# LMD18200.net
KiCad netlist of a schematic drawn in EAGLE
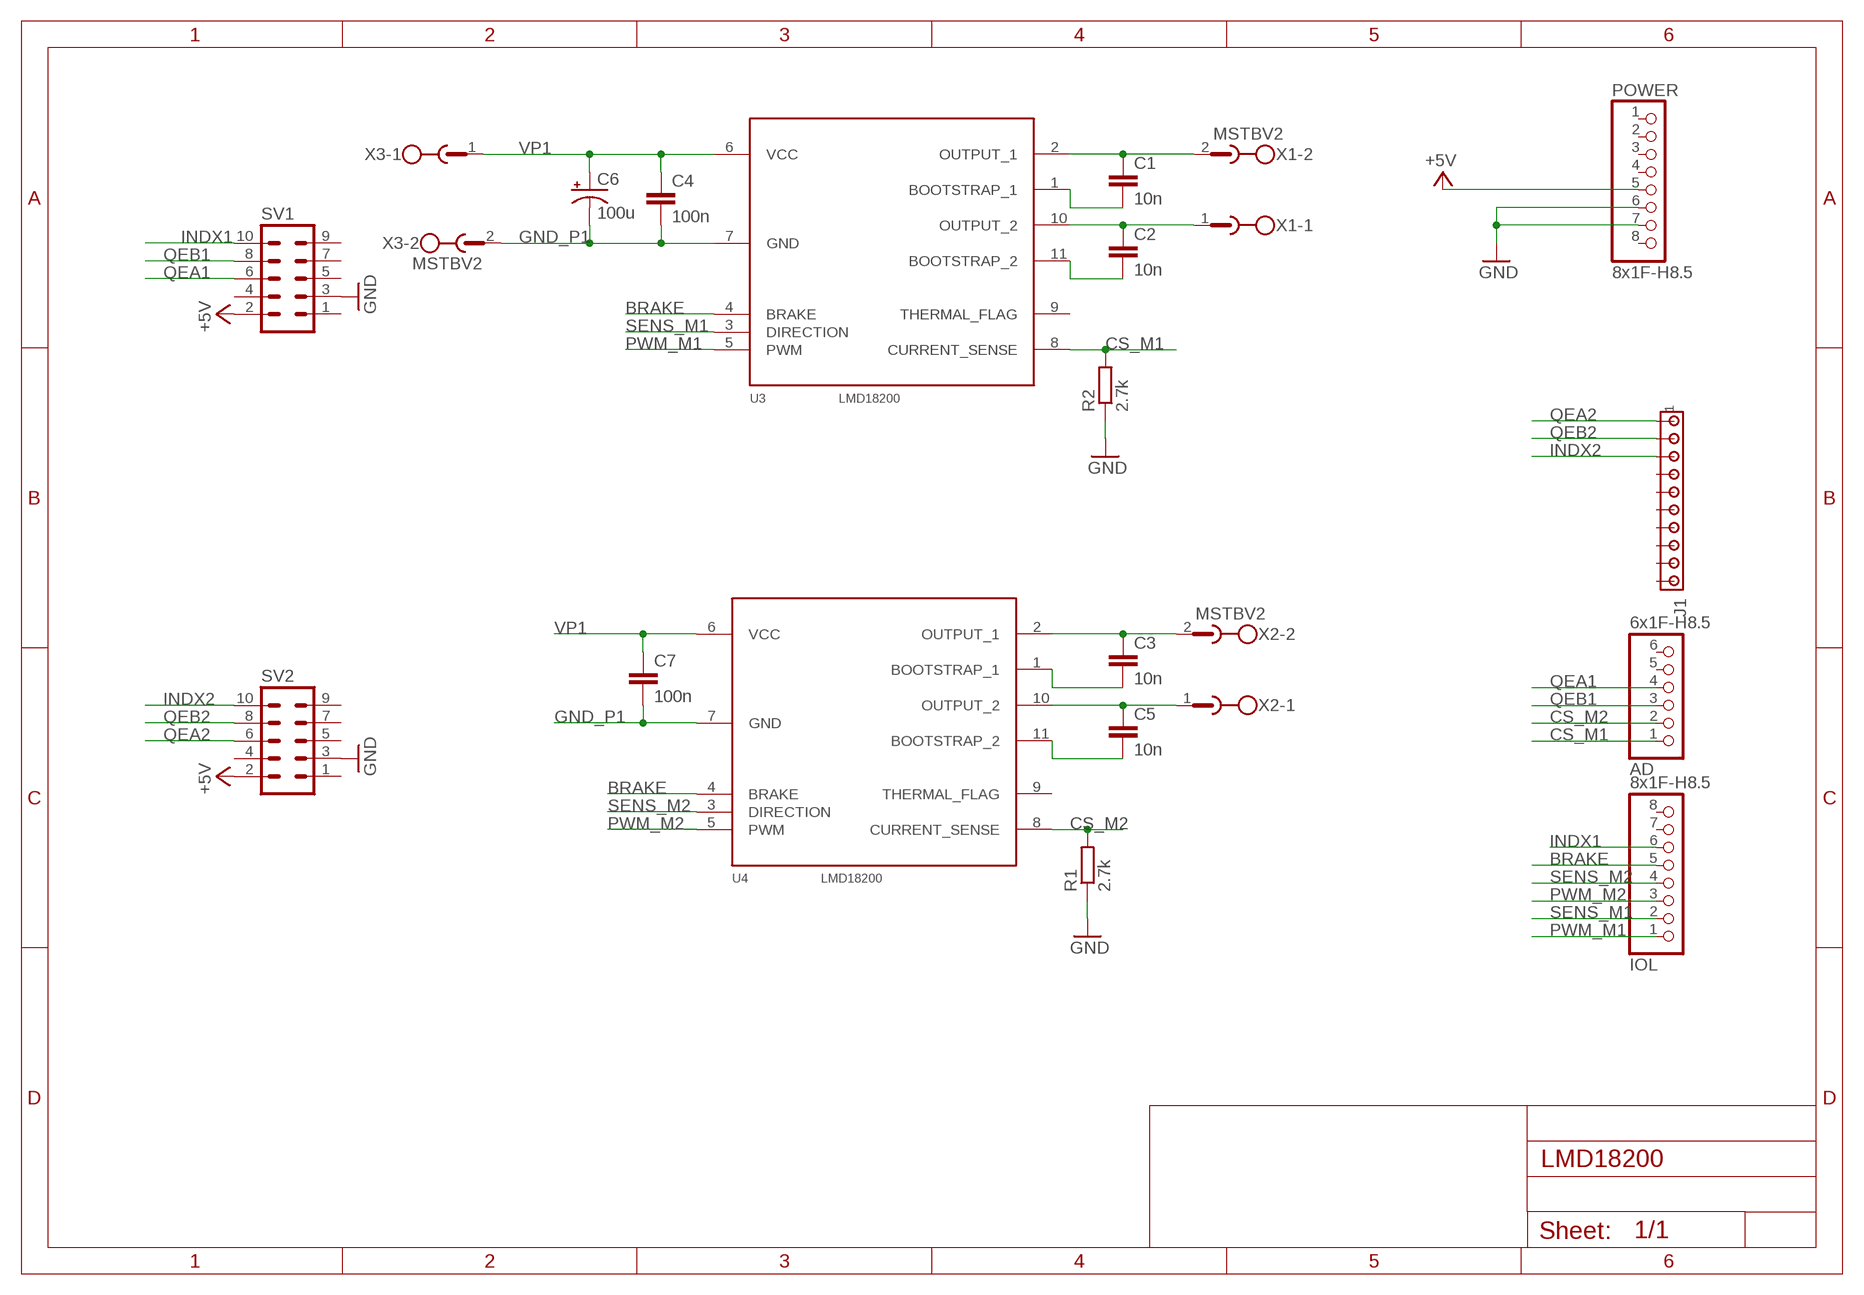
[diagram p0: schematic, sheet 1]

(export (version "E")
  (design (tool "Eeschema 10.0.6"))
  (components
    (comp (ref "AD")
      (value "6x1F-H8.5")
      (footprint "eagle-import:1X06")
      (libsource (lib "eagle-import") (part "PINHD-1X6"))
    )
    (comp (ref "C1")
      (value "10n")
      (footprint "eagle-import:C0603")
      (libsource (lib "eagle-import") (part "C-EUC0603"))
    )
    (comp (ref "C2")
      (value "10n")
      (footprint "eagle-import:C0603")
      (libsource (lib "eagle-import") (part "C-EUC0603"))
    )
    (comp (ref "C3")
      (value "10n")
      (footprint "eagle-import:C0603")
      (libsource (lib "eagle-import") (part "C-EUC0603"))
    )
    (comp (ref "C4")
      (value "100n")
      (footprint "eagle-import:C0603")
      (libsource (lib "eagle-import") (part "C-EUC0603"))
    )
    (comp (ref "C5")
      (value "10n")
      (footprint "eagle-import:C0603")
      (libsource (lib "eagle-import") (part "C-EUC0603"))
    )
    (comp (ref "C6")
      (value "100u")
      (footprint "eagle-import:E5-13")
      (libsource (lib "eagle-import") (part "CPOL-USE5-13"))
    )
    (comp (ref "C7")
      (value "100n")
      (footprint "eagle-import:C0603")
      (libsource (lib "eagle-import") (part "C-EUC0603"))
    )
    (comp (ref "IOL")
      (value "8x1F-H8.5")
      (footprint "eagle-import:1X08")
      (libsource (lib "eagle-import") (part "PINHD-1X8"))
    )
    (comp (ref "J1")
      (value "MTA10-100")
      (footprint "eagle-import:10X10MTA")
      (libsource (lib "eagle-import") (part "MTA10-100"))
    )
    (comp (ref "POWER")
      (value "8x1F-H8.5")
      (footprint "eagle-import:1X08")
      (libsource (lib "eagle-import") (part "PINHD-1X8"))
    )
    (comp (ref "R1")
      (value "2.7k")
      (footprint "eagle-import:R0805")
      (libsource (lib "eagle-import") (part "R-EU_R0805"))
    )
    (comp (ref "R2")
      (value "2.7k")
      (footprint "eagle-import:R0805")
      (libsource (lib "eagle-import") (part "R-EU_R0805"))
    )
    (comp (ref "SV1")
      (value "ML10L")
      (footprint "eagle-import:ML10L")
      (libsource (lib "eagle-import") (part "ML10L"))
    )
    (comp (ref "SV2")
      (value "ML10L")
      (footprint "eagle-import:ML10L")
      (libsource (lib "eagle-import") (part "ML10L"))
    )
    (comp (ref "U3")
      (value "LMD18200")
      (footprint "eagle-import:TO-220-11_C")
      (libsource (lib "eagle-import") (part "LMD18200"))
    )
    (comp (ref "U4")
      (value "LMD18200")
      (footprint "eagle-import:TO-220-11_C")
      (libsource (lib "eagle-import") (part "LMD18200"))
    )
    (comp (ref "X1")
      (value "MSTBV2")
      (footprint "eagle-import:MSTBV2")
      (fields (field (name "MPN") "MSTBV 2,5/2-GF-5.08"))
      (libsource (lib "eagle-import") (part "MSTBV2"))
    )
    (comp (ref "X2")
      (value "MSTBV2")
      (footprint "eagle-import:MSTBV2")
      (fields (field (name "MPN") "MSTBV 2,5/2-GF-5.08"))
      (libsource (lib "eagle-import") (part "MSTBV2"))
    )
    (comp (ref "X3")
      (value "MSTBV2")
      (footprint "eagle-import:MSTBV2")
      (fields (field (name "MPN") "MSTBV 2,5/2-GF-5.08"))
      (libsource (lib "eagle-import") (part "MSTBV2"))
    )
  )
  (nets
    (net (code "1") (name "+5V") (class "Default")
      (node (ref "POWER") (pin "5") (pinfunction "5_5") (pintype "passive"))
      (node (ref "SV1") (pin "2") (pinfunction "2_2") (pintype "passive"))
      (node (ref "SV2") (pin "2") (pinfunction "2_2") (pintype "passive"))
    )
    (net (code "2") (name "/BRAKE") (class "Default")
      (node (ref "IOL") (pin "5") (pinfunction "5_5") (pintype "passive"))
      (node (ref "U3") (pin "4") (pinfunction "BRAKE_4") (pintype "input"))
      (node (ref "U4") (pin "4") (pinfunction "BRAKE_4") (pintype "input"))
    )
    (net (code "3") (name "/CS_M1") (class "Default")
      (node (ref "AD") (pin "1") (pinfunction "1_1") (pintype "passive"))
      (node (ref "R2") (pin "2") (pinfunction "2_2") (pintype "passive"))
      (node (ref "U3") (pin "8") (pinfunction "CURRENT_SENSE_8") (pintype "output"))
    )
    (net (code "4") (name "/CS_M2") (class "Default")
      (node (ref "AD") (pin "2") (pinfunction "2_2") (pintype "passive"))
      (node (ref "R1") (pin "2") (pinfunction "2_2") (pintype "passive"))
      (node (ref "U4") (pin "8") (pinfunction "CURRENT_SENSE_8") (pintype "output"))
    )
    (net (code "5") (name "/GND_P1") (class "Default")
      (node (ref "C4") (pin "2") (pinfunction "2_2") (pintype "passive"))
      (node (ref "C6") (pin "-") (pinfunction "-_-") (pintype "passive"))
      (node (ref "C7") (pin "2") (pinfunction "2_2") (pintype "passive"))
      (node (ref "U3") (pin "7") (pinfunction "GND_7") (pintype "power_in"))
      (node (ref "U4") (pin "7") (pinfunction "GND_7") (pintype "power_in"))
      (node (ref "X3") (pin "2") (pinfunction "1_2") (pintype "passive"))
    )
    (net (code "6") (name "/INDX1") (class "Default")
      (node (ref "IOL") (pin "6") (pinfunction "6_6") (pintype "passive"))
      (node (ref "SV1") (pin "10") (pinfunction "10_10") (pintype "passive"))
    )
    (net (code "7") (name "/INDX2") (class "Default")
      (node (ref "J1") (pin "3") (pinfunction "3_3") (pintype "passive"))
      (node (ref "SV2") (pin "10") (pinfunction "10_10") (pintype "passive"))
    )
    (net (code "8") (name "/PWM_M1") (class "Default")
      (node (ref "IOL") (pin "1") (pinfunction "1_1") (pintype "passive"))
      (node (ref "U3") (pin "5") (pinfunction "PWM_5") (pintype "input"))
    )
    (net (code "9") (name "/PWM_M2") (class "Default")
      (node (ref "IOL") (pin "3") (pinfunction "3_3") (pintype "passive"))
      (node (ref "U4") (pin "5") (pinfunction "PWM_5") (pintype "input"))
    )
    (net (code "10") (name "/QEA1") (class "Default")
      (node (ref "AD") (pin "4") (pinfunction "4_4") (pintype "passive"))
      (node (ref "SV1") (pin "6") (pinfunction "6_6") (pintype "passive"))
    )
    (net (code "11") (name "/QEA2") (class "Default")
      (node (ref "J1") (pin "1") (pinfunction "1_1") (pintype "passive"))
      (node (ref "SV2") (pin "6") (pinfunction "6_6") (pintype "passive"))
    )
    (net (code "12") (name "/QEB1") (class "Default")
      (node (ref "AD") (pin "3") (pinfunction "3_3") (pintype "passive"))
      (node (ref "SV1") (pin "8") (pinfunction "8_8") (pintype "passive"))
    )
    (net (code "13") (name "/QEB2") (class "Default")
      (node (ref "J1") (pin "2") (pinfunction "2_2") (pintype "passive"))
      (node (ref "SV2") (pin "8") (pinfunction "8_8") (pintype "passive"))
    )
    (net (code "14") (name "/SENS_M1") (class "Default")
      (node (ref "IOL") (pin "2") (pinfunction "2_2") (pintype "passive"))
      (node (ref "U3") (pin "3") (pinfunction "DIRECTION_3") (pintype "input"))
    )
    (net (code "15") (name "/SENS_M2") (class "Default")
      (node (ref "IOL") (pin "4") (pinfunction "4_4") (pintype "passive"))
      (node (ref "U4") (pin "3") (pinfunction "DIRECTION_3") (pintype "input"))
    )
    (net (code "16") (name "/VP1") (class "Default")
      (node (ref "C4") (pin "1") (pinfunction "1_1") (pintype "passive"))
      (node (ref "C6") (pin "+") (pinfunction "+_+") (pintype "passive"))
      (node (ref "C7") (pin "1") (pinfunction "1_1") (pintype "passive"))
      (node (ref "U3") (pin "6") (pinfunction "VCC_6") (pintype "power_in"))
      (node (ref "U4") (pin "6") (pinfunction "VCC_6") (pintype "power_in"))
      (node (ref "X3") (pin "1") (pinfunction "1_1") (pintype "passive"))
    )
    (net (code "17") (name "GND") (class "Default")
      (node (ref "POWER") (pin "6") (pinfunction "6_6") (pintype "passive"))
      (node (ref "POWER") (pin "7") (pinfunction "7_7") (pintype "passive"))
      (node (ref "R1") (pin "1") (pinfunction "1_1") (pintype "passive"))
      (node (ref "R2") (pin "1") (pinfunction "1_1") (pintype "passive"))
      (node (ref "SV1") (pin "3") (pinfunction "3_3") (pintype "passive"))
      (node (ref "SV2") (pin "3") (pinfunction "3_3") (pintype "passive"))
    )
    (net (code "18") (name "Net-(U3-BOOTSTRAP_1)") (class "Default")
      (node (ref "C1") (pin "2") (pinfunction "2_2") (pintype "passive"))
      (node (ref "U3") (pin "1") (pinfunction "BOOTSTRAP_1_1") (pintype "output"))
    )
    (net (code "19") (name "Net-(U3-BOOTSTRAP_2)") (class "Default")
      (node (ref "C2") (pin "2") (pinfunction "2_2") (pintype "passive"))
      (node (ref "U3") (pin "11") (pinfunction "BOOTSTRAP_2_11") (pintype "output"))
    )
    (net (code "20") (name "Net-(U3-OUTPUT_1)") (class "Default")
      (node (ref "C1") (pin "1") (pinfunction "1_1") (pintype "passive"))
      (node (ref "U3") (pin "2") (pinfunction "OUTPUT_1_2") (pintype "output"))
      (node (ref "X1") (pin "2") (pinfunction "1_2") (pintype "passive"))
    )
    (net (code "21") (name "Net-(U3-OUTPUT_2)") (class "Default")
      (node (ref "C2") (pin "1") (pinfunction "1_1") (pintype "passive"))
      (node (ref "U3") (pin "10") (pinfunction "OUTPUT_2_10") (pintype "output"))
      (node (ref "X1") (pin "1") (pinfunction "1_1") (pintype "passive"))
    )
    (net (code "22") (name "Net-(U4-BOOTSTRAP_1)") (class "Default")
      (node (ref "C3") (pin "2") (pinfunction "2_2") (pintype "passive"))
      (node (ref "U4") (pin "1") (pinfunction "BOOTSTRAP_1_1") (pintype "output"))
    )
    (net (code "23") (name "Net-(U4-BOOTSTRAP_2)") (class "Default")
      (node (ref "C5") (pin "2") (pinfunction "2_2") (pintype "passive"))
      (node (ref "U4") (pin "11") (pinfunction "BOOTSTRAP_2_11") (pintype "output"))
    )
    (net (code "24") (name "Net-(U4-OUTPUT_1)") (class "Default")
      (node (ref "C3") (pin "1") (pinfunction "1_1") (pintype "passive"))
      (node (ref "U4") (pin "2") (pinfunction "OUTPUT_1_2") (pintype "output"))
      (node (ref "X2") (pin "2") (pinfunction "1_2") (pintype "passive"))
    )
    (net (code "25") (name "Net-(U4-OUTPUT_2)") (class "Default")
      (node (ref "C5") (pin "1") (pinfunction "1_1") (pintype "passive"))
      (node (ref "U4") (pin "10") (pinfunction "OUTPUT_2_10") (pintype "output"))
      (node (ref "X2") (pin "1") (pinfunction "1_1") (pintype "passive"))
    )
    (net (code "26") (name "unconnected-(AD-Pad5)") (class "Default")
      (node (ref "AD") (pin "5") (pinfunction "5_5") (pintype "passive"))
    )
    (net (code "27") (name "unconnected-(AD-Pad6)") (class "Default")
      (node (ref "AD") (pin "6") (pinfunction "6_6") (pintype "passive"))
    )
    (net (code "28") (name "unconnected-(IOL-Pad7)") (class "Default")
      (node (ref "IOL") (pin "7") (pinfunction "7_7") (pintype "passive"))
    )
    (net (code "29") (name "unconnected-(IOL-Pad8)") (class "Default")
      (node (ref "IOL") (pin "8") (pinfunction "8_8") (pintype "passive"))
    )
    (net (code "30") (name "unconnected-(J1-Pad4)") (class "Default")
      (node (ref "J1") (pin "4") (pinfunction "4_4") (pintype "passive"))
    )
    (net (code "31") (name "unconnected-(J1-Pad5)") (class "Default")
      (node (ref "J1") (pin "5") (pinfunction "5_5") (pintype "passive"))
    )
    (net (code "32") (name "unconnected-(J1-Pad6)") (class "Default")
      (node (ref "J1") (pin "6") (pinfunction "6_6") (pintype "passive"))
    )
    (net (code "33") (name "unconnected-(J1-Pad7)") (class "Default")
      (node (ref "J1") (pin "7") (pinfunction "7_7") (pintype "passive"))
    )
    (net (code "34") (name "unconnected-(J1-Pad8)") (class "Default")
      (node (ref "J1") (pin "8") (pinfunction "8_8") (pintype "passive"))
    )
    (net (code "35") (name "unconnected-(J1-Pad9)") (class "Default")
      (node (ref "J1") (pin "9") (pinfunction "9_9") (pintype "passive"))
    )
    (net (code "36") (name "unconnected-(J1-Pad10)") (class "Default")
      (node (ref "J1") (pin "10") (pinfunction "10_10") (pintype "passive"))
    )
    (net (code "37") (name "unconnected-(POWER-Pad1)") (class "Default")
      (node (ref "POWER") (pin "1") (pinfunction "1_1") (pintype "passive"))
    )
    (net (code "38") (name "unconnected-(POWER-Pad2)") (class "Default")
      (node (ref "POWER") (pin "2") (pinfunction "2_2") (pintype "passive"))
    )
    (net (code "39") (name "unconnected-(POWER-Pad3)") (class "Default")
      (node (ref "POWER") (pin "3") (pinfunction "3_3") (pintype "passive"))
    )
    (net (code "40") (name "unconnected-(POWER-Pad4)") (class "Default")
      (node (ref "POWER") (pin "4") (pinfunction "4_4") (pintype "passive"))
    )
    (net (code "41") (name "unconnected-(POWER-Pad8)") (class "Default")
      (node (ref "POWER") (pin "8") (pinfunction "8_8") (pintype "passive"))
    )
    (net (code "42") (name "unconnected-(SV1-Pad1)") (class "Default")
      (node (ref "SV1") (pin "1") (pinfunction "1_1") (pintype "passive"))
    )
    (net (code "43") (name "unconnected-(SV1-Pad4)") (class "Default")
      (node (ref "SV1") (pin "4") (pinfunction "4_4") (pintype "passive"))
    )
    (net (code "44") (name "unconnected-(SV1-Pad5)") (class "Default")
      (node (ref "SV1") (pin "5") (pinfunction "5_5") (pintype "passive"))
    )
    (net (code "45") (name "unconnected-(SV1-Pad7)") (class "Default")
      (node (ref "SV1") (pin "7") (pinfunction "7_7") (pintype "passive"))
    )
    (net (code "46") (name "unconnected-(SV1-Pad9)") (class "Default")
      (node (ref "SV1") (pin "9") (pinfunction "9_9") (pintype "passive"))
    )
    (net (code "47") (name "unconnected-(SV2-Pad1)") (class "Default")
      (node (ref "SV2") (pin "1") (pinfunction "1_1") (pintype "passive"))
    )
    (net (code "48") (name "unconnected-(SV2-Pad4)") (class "Default")
      (node (ref "SV2") (pin "4") (pinfunction "4_4") (pintype "passive"))
    )
    (net (code "49") (name "unconnected-(SV2-Pad5)") (class "Default")
      (node (ref "SV2") (pin "5") (pinfunction "5_5") (pintype "passive"))
    )
    (net (code "50") (name "unconnected-(SV2-Pad7)") (class "Default")
      (node (ref "SV2") (pin "7") (pinfunction "7_7") (pintype "passive"))
    )
    (net (code "51") (name "unconnected-(SV2-Pad9)") (class "Default")
      (node (ref "SV2") (pin "9") (pinfunction "9_9") (pintype "passive"))
    )
    (net (code "52") (name "unconnected-(U3-THERMAL_FLAG-Pad9)") (class "Default")
      (node (ref "U3") (pin "9") (pinfunction "THERMAL_FLAG_9") (pintype "output"))
    )
    (net (code "53") (name "unconnected-(U4-THERMAL_FLAG-Pad9)") (class "Default")
      (node (ref "U4") (pin "9") (pinfunction "THERMAL_FLAG_9") (pintype "output"))
    )
  )
)
